# ATTinyAmpDriver.net
KiCad netlist of a schematic drawn in EAGLE
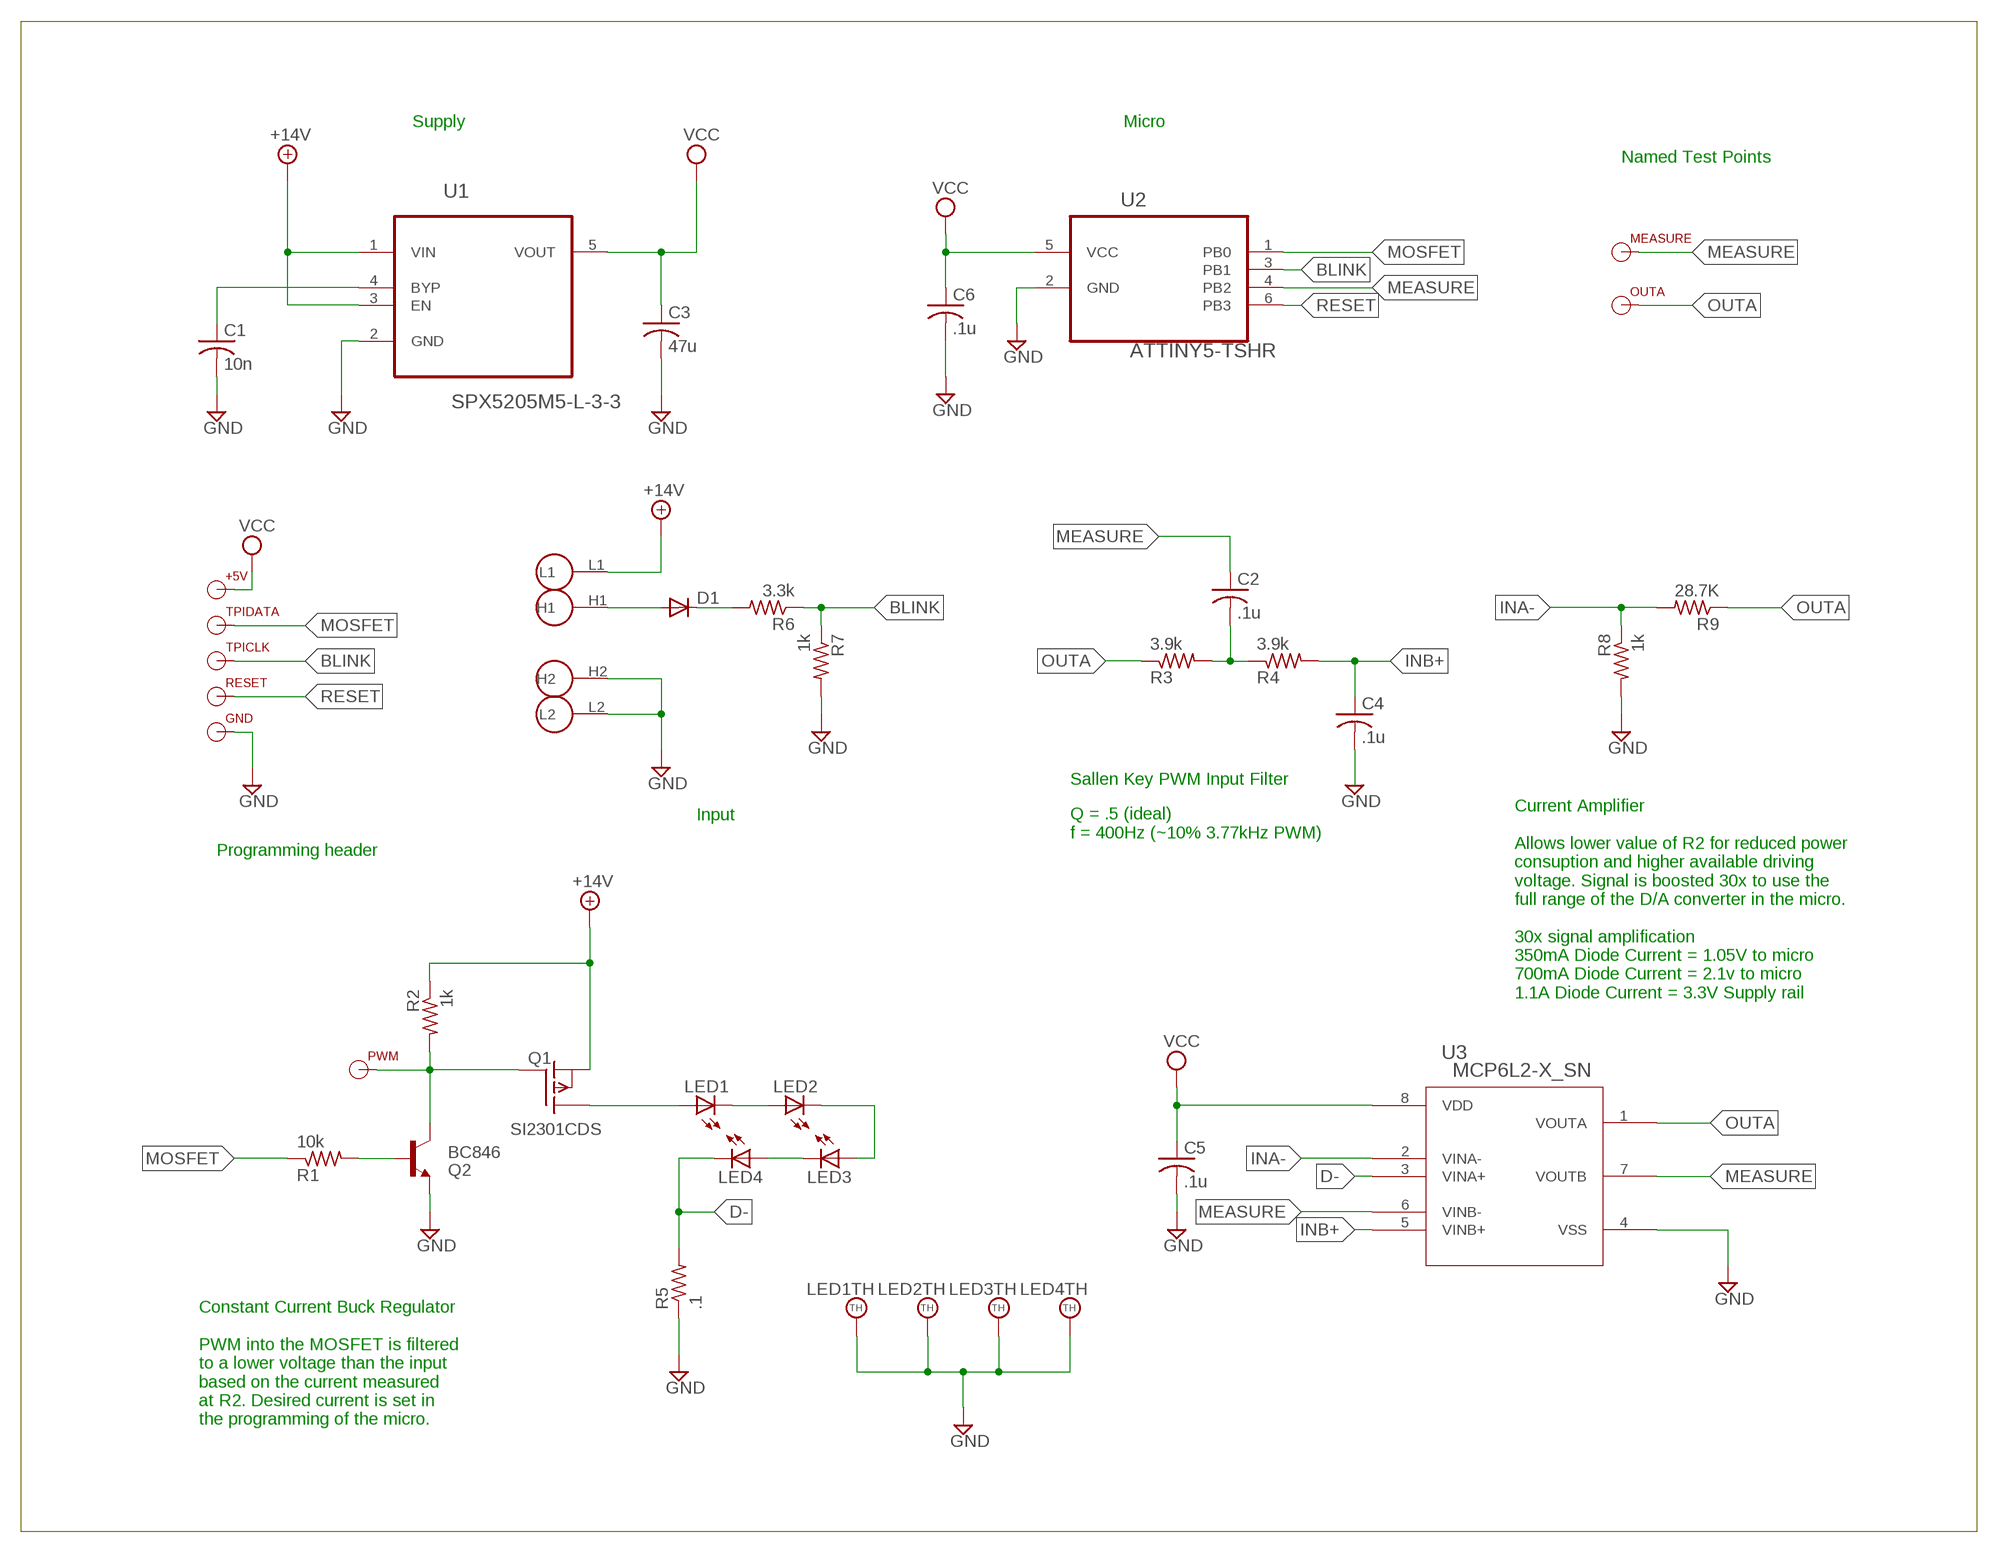
[diagram p0: schematic, sheet 1]

(export (version "E")
  (design (tool "Eeschema 10.0.6"))
  (components
    (comp (ref "+5V")
      (value "TPI")
      (footprint "eagle-import:TPI_PAD")
      (libsource (lib "eagle-import") (part "TPI"))
    )
    (comp (ref "C1")
      (value "10n")
      (footprint "eagle-import:C0603")
      (libsource (lib "eagle-import") (part "C-USC0603"))
    )
    (comp (ref "C2")
      (value ".1u")
      (footprint "eagle-import:C0603")
      (libsource (lib "eagle-import") (part "C-USC0603"))
    )
    (comp (ref "C3")
      (value "47u")
      (footprint "eagle-import:C1206")
      (libsource (lib "eagle-import") (part "C-USC1206"))
    )
    (comp (ref "C4")
      (value ".1u")
      (footprint "eagle-import:C0603")
      (libsource (lib "eagle-import") (part "C-USC0603"))
    )
    (comp (ref "C5")
      (value ".1u")
      (footprint "eagle-import:C0603")
      (libsource (lib "eagle-import") (part "C-USC0603"))
    )
    (comp (ref "C6")
      (value ".1u")
      (footprint "eagle-import:C0603")
      (libsource (lib "eagle-import") (part "C-USC0603"))
    )
    (comp (ref "D1")
      (value "DIODE_0603")
      (footprint "eagle-import:D0603")
      (libsource (lib "eagle-import") (part "DIODE_0603"))
    )
    (comp (ref "GND")
      (value "TPI")
      (footprint "eagle-import:TPI_PAD")
      (libsource (lib "eagle-import") (part "TPI"))
    )
    (comp (ref "LED1")
      (value "LUXEON_REBELCREE_XP-E")
      (footprint "eagle-import:CREE_XP-E")
      (libsource (lib "eagle-import") (part "LUXEON_REBELCREE_XP-E"))
    )
    (comp (ref "LED2")
      (value "LUXEON_REBELCREE_XP-E")
      (footprint "eagle-import:CREE_XP-E")
      (libsource (lib "eagle-import") (part "LUXEON_REBELCREE_XP-E"))
    )
    (comp (ref "LED3")
      (value "LUXEON_REBELCREE_XP-E")
      (footprint "eagle-import:CREE_XP-E")
      (libsource (lib "eagle-import") (part "LUXEON_REBELCREE_XP-E"))
    )
    (comp (ref "LED4")
      (value "LUXEON_REBELCREE_XP-E")
      (footprint "eagle-import:CREE_XP-E")
      (libsource (lib "eagle-import") (part "LUXEON_REBELCREE_XP-E"))
    )
    (comp (ref "MEASURE")
      (value "TPI")
      (footprint "eagle-import:TPI_PAD")
      (libsource (lib "eagle-import") (part "TPI"))
    )
    (comp (ref "OUTA")
      (value "TPI")
      (footprint "eagle-import:TPI_PAD")
      (libsource (lib "eagle-import") (part "TPI"))
    )
    (comp (ref "PWM")
      (value "TPI")
      (footprint "eagle-import:TPI_PAD")
      (libsource (lib "eagle-import") (part "TPI"))
    )
    (comp (ref "Q1")
      (value "SI2301CDS")
      (footprint "eagle-import:SOT-23_POWER")
      (libsource (lib "eagle-import") (part "SI2301CDS"))
    )
    (comp (ref "Q2")
      (value "BC846")
      (footprint "eagle-import:SOT23")
      (libsource (lib "eagle-import") (part "BC846"))
    )
    (comp (ref "R1")
      (value "10k")
      (footprint "eagle-import:R0603")
      (libsource (lib "eagle-import") (part "R-US_R0603"))
    )
    (comp (ref "R2")
      (value "1k")
      (footprint "eagle-import:R0603")
      (libsource (lib "eagle-import") (part "R-US_R0603"))
    )
    (comp (ref "R3")
      (value "3.9k")
      (footprint "eagle-import:R0603")
      (libsource (lib "eagle-import") (part "R-US_R0603"))
    )
    (comp (ref "R4")
      (value "3.9k")
      (footprint "eagle-import:R0603")
      (libsource (lib "eagle-import") (part "R-US_R0603"))
    )
    (comp (ref "R5")
      (value ".1")
      (footprint "eagle-import:R1206")
      (libsource (lib "eagle-import") (part "R-US_R1206"))
    )
    (comp (ref "R6")
      (value "3.3k")
      (footprint "eagle-import:R0603")
      (libsource (lib "eagle-import") (part "R-US_R0603"))
    )
    (comp (ref "R7")
      (value "1k")
      (footprint "eagle-import:R0603")
      (libsource (lib "eagle-import") (part "R-US_R0603"))
    )
    (comp (ref "R8")
      (value "1k")
      (footprint "eagle-import:R0603")
      (libsource (lib "eagle-import") (part "R-US_R0603"))
    )
    (comp (ref "R9")
      (value "28.7K")
      (footprint "eagle-import:R0603")
      (libsource (lib "eagle-import") (part "R-US_R0603"))
    )
    (comp (ref "RESET")
      (value "TPI")
      (footprint "eagle-import:TPI_PAD")
      (libsource (lib "eagle-import") (part "TPI"))
    )
    (comp (ref "TPICLK")
      (value "TPI")
      (footprint "eagle-import:TPI_PAD")
      (libsource (lib "eagle-import") (part "TPI"))
    )
    (comp (ref "TPIDATA")
      (value "TPI")
      (footprint "eagle-import:TPI_PAD")
      (libsource (lib "eagle-import") (part "TPI"))
    )
    (comp (ref "U$1")
      (value "CON_TAILLIGHT")
      (footprint "eagle-import:TAILLIGHT")
      (libsource (lib "eagle-import") (part "CON_TAILLIGHT"))
    )
    (comp (ref "U1")
      (value "SPX5205M5-L-3-3")
      (footprint "eagle-import:SOT95P280X145-5N")
      (libsource (lib "eagle-import") (part "SPX5205M5-L-3-3"))
    )
    (comp (ref "U2")
      (value "ATTINY5-TSHR")
      (footprint "eagle-import:SOT95P280X145-6N")
      (libsource (lib "eagle-import") (part "ATTINY5-TSHR"))
    )
    (comp (ref "U3")
      (value "MCP6L2-X_SN")
      (footprint "eagle-import:SOIC8-N_MC")
      (libsource (lib "eagle-import") (part "MCP6L2-X_SN"))
    )
  )
  (nets
    (net (code "1") (name "+14V") (class "Default")
      (node (ref "Q1") (pin "P$2") (pinfunction "S_P$2") (pintype "passive"))
      (node (ref "R2") (pin "1") (pinfunction "1_1") (pintype "passive"))
      (node (ref "U$1") (pin "L1") (pinfunction "L1_L1") (pintype "bidirectional"))
      (node (ref "U1") (pin "1") (pinfunction "VIN_1") (pintype "power_in"))
      (node (ref "U1") (pin "3") (pinfunction "EN_3") (pintype "input"))
    )
    (net (code "2") (name "BLINK") (class "Default")
      (node (ref "R6") (pin "1") (pinfunction "1_1") (pintype "passive"))
      (node (ref "R7") (pin "1") (pinfunction "1_1") (pintype "passive"))
      (node (ref "TPICLK") (pin "P$1") (pinfunction "TPI_PIN_P$1") (pintype "bidirectional"))
      (node (ref "U2") (pin "3") (pinfunction "PB1_3") (pintype "bidirectional"))
    )
    (net (code "3") (name "D-") (class "Default")
      (node (ref "LED4") (pin "CT") (pinfunction "C_CT") (pintype "passive"))
      (node (ref "R5") (pin "2") (pinfunction "2_2") (pintype "passive"))
      (node (ref "U3") (pin "3") (pinfunction "VINA+_3") (pintype "passive"))
    )
    (net (code "4") (name "GND") (class "Default")
      (node (ref "C1") (pin "2") (pinfunction "2_2") (pintype "passive"))
      (node (ref "C3") (pin "2") (pinfunction "2_2") (pintype "passive"))
      (node (ref "C4") (pin "2") (pinfunction "2_2") (pintype "passive"))
      (node (ref "C5") (pin "2") (pinfunction "2_2") (pintype "passive"))
      (node (ref "C6") (pin "2") (pinfunction "2_2") (pintype "passive"))
      (node (ref "GND") (pin "P$1") (pinfunction "TPI_PIN_P$1") (pintype "bidirectional"))
      (node (ref "LED1") (pin "TH") (pinfunction "TH_TH") (pintype "passive"))
      (node (ref "LED2") (pin "TH") (pinfunction "TH_TH") (pintype "passive"))
      (node (ref "LED3") (pin "TH") (pinfunction "TH_TH") (pintype "passive"))
      (node (ref "LED4") (pin "TH") (pinfunction "TH_TH") (pintype "passive"))
      (node (ref "Q2") (pin "2") (pinfunction "E_2") (pintype "passive"))
      (node (ref "R5") (pin "1") (pinfunction "1_1") (pintype "passive"))
      (node (ref "R7") (pin "2") (pinfunction "2_2") (pintype "passive"))
      (node (ref "R8") (pin "2") (pinfunction "2_2") (pintype "passive"))
      (node (ref "U$1") (pin "H2") (pinfunction "H2_H2") (pintype "bidirectional"))
      (node (ref "U$1") (pin "L2") (pinfunction "L2_L2") (pintype "bidirectional"))
      (node (ref "U1") (pin "2") (pinfunction "GND_2") (pintype "passive"))
      (node (ref "U2") (pin "2") (pinfunction "GND_2") (pintype "passive"))
      (node (ref "U3") (pin "4") (pinfunction "VSS_4") (pintype "passive"))
    )
    (net (code "5") (name "INA-") (class "Default")
      (node (ref "R8") (pin "1") (pinfunction "1_1") (pintype "passive"))
      (node (ref "R9") (pin "2") (pinfunction "2_2") (pintype "passive"))
      (node (ref "U3") (pin "2") (pinfunction "VINA-_2") (pintype "passive"))
    )
    (net (code "6") (name "INB+") (class "Default")
      (node (ref "C4") (pin "1") (pinfunction "1_1") (pintype "passive"))
      (node (ref "R4") (pin "2") (pinfunction "2_2") (pintype "passive"))
      (node (ref "U3") (pin "5") (pinfunction "VINB+_5") (pintype "passive"))
    )
    (net (code "7") (name "MEASURE") (class "Default")
      (node (ref "C2") (pin "1") (pinfunction "1_1") (pintype "passive"))
      (node (ref "MEASURE") (pin "P$1") (pinfunction "TPI_PIN_P$1") (pintype "bidirectional"))
      (node (ref "U2") (pin "4") (pinfunction "PB2_4") (pintype "bidirectional"))
      (node (ref "U3") (pin "6") (pinfunction "VINB-_6") (pintype "passive"))
      (node (ref "U3") (pin "7") (pinfunction "VOUTB_7") (pintype "passive"))
    )
    (net (code "8") (name "MOSFET") (class "Default")
      (node (ref "R1") (pin "1") (pinfunction "1_1") (pintype "passive"))
      (node (ref "TPIDATA") (pin "P$1") (pinfunction "TPI_PIN_P$1") (pintype "bidirectional"))
      (node (ref "U2") (pin "1") (pinfunction "PB0_1") (pintype "bidirectional"))
    )
    (net (code "9") (name "Net-(C2-Pad2)") (class "Default")
      (node (ref "C2") (pin "2") (pinfunction "2_2") (pintype "passive"))
      (node (ref "R3") (pin "2") (pinfunction "2_2") (pintype "passive"))
      (node (ref "R4") (pin "1") (pinfunction "1_1") (pintype "passive"))
    )
    (net (code "10") (name "Net-(D1-A)") (class "Default")
      (node (ref "D1") (pin "1A") (pinfunction "A_1A") (pintype "passive"))
      (node (ref "U$1") (pin "H1") (pinfunction "H1_H1") (pintype "bidirectional"))
    )
    (net (code "11") (name "Net-(D1-C)") (class "Default")
      (node (ref "D1") (pin "2C") (pinfunction "C_2C") (pintype "passive"))
      (node (ref "R6") (pin "2") (pinfunction "2_2") (pintype "passive"))
    )
    (net (code "12") (name "Net-(LED1A-A)") (class "Default")
      (node (ref "LED1") (pin "AN") (pinfunction "A_AN") (pintype "passive"))
      (node (ref "Q1") (pin "P$3") (pinfunction "D_P$3") (pintype "passive"))
    )
    (net (code "13") (name "Net-(LED1A-C)") (class "Default")
      (node (ref "LED1") (pin "CT") (pinfunction "C_CT") (pintype "passive"))
      (node (ref "LED2") (pin "AN") (pinfunction "A_AN") (pintype "passive"))
    )
    (net (code "14") (name "Net-(LED2A-C)") (class "Default")
      (node (ref "LED2") (pin "CT") (pinfunction "C_CT") (pintype "passive"))
      (node (ref "LED3") (pin "AN") (pinfunction "A_AN") (pintype "passive"))
    )
    (net (code "15") (name "Net-(LED3A-C)") (class "Default")
      (node (ref "LED3") (pin "CT") (pinfunction "C_CT") (pintype "passive"))
      (node (ref "LED4") (pin "AN") (pinfunction "A_AN") (pintype "passive"))
    )
    (net (code "16") (name "Net-(PWM-TPI_PIN)") (class "Default")
      (node (ref "PWM") (pin "P$1") (pinfunction "TPI_PIN_P$1") (pintype "bidirectional"))
      (node (ref "Q1") (pin "P$1") (pinfunction "G_P$1") (pintype "passive"))
      (node (ref "Q2") (pin "3") (pinfunction "C_3") (pintype "passive"))
      (node (ref "R2") (pin "2") (pinfunction "2_2") (pintype "passive"))
    )
    (net (code "17") (name "Net-(Q2-B)") (class "Default")
      (node (ref "Q2") (pin "1") (pinfunction "B_1") (pintype "passive"))
      (node (ref "R1") (pin "2") (pinfunction "2_2") (pintype "passive"))
    )
    (net (code "18") (name "Net-(U1-BYP)") (class "Default")
      (node (ref "C1") (pin "1") (pinfunction "1_1") (pintype "passive"))
      (node (ref "U1") (pin "4") (pinfunction "BYP_4") (pintype "input"))
    )
    (net (code "19") (name "OUTA") (class "Default")
      (node (ref "OUTA") (pin "P$1") (pinfunction "TPI_PIN_P$1") (pintype "bidirectional"))
      (node (ref "R3") (pin "1") (pinfunction "1_1") (pintype "passive"))
      (node (ref "R9") (pin "1") (pinfunction "1_1") (pintype "passive"))
      (node (ref "U3") (pin "1") (pinfunction "VOUTA_1") (pintype "passive"))
    )
    (net (code "20") (name "RESET") (class "Default")
      (node (ref "RESET") (pin "P$1") (pinfunction "TPI_PIN_P$1") (pintype "bidirectional"))
      (node (ref "U2") (pin "6") (pinfunction "PB3_6") (pintype "bidirectional"))
    )
    (net (code "21") (name "VCC") (class "Default")
      (node (ref "+5V") (pin "P$1") (pinfunction "TPI_PIN_P$1") (pintype "bidirectional"))
      (node (ref "C3") (pin "1") (pinfunction "1_1") (pintype "passive"))
      (node (ref "C5") (pin "1") (pinfunction "1_1") (pintype "passive"))
      (node (ref "C6") (pin "1") (pinfunction "1_1") (pintype "passive"))
      (node (ref "U1") (pin "5") (pinfunction "VOUT_5") (pintype "output"))
      (node (ref "U2") (pin "5") (pinfunction "VCC_5") (pintype "power_in"))
      (node (ref "U3") (pin "8") (pinfunction "VDD_8") (pintype "passive"))
    )
  )
)
